# fpc_cable_all.net
KiCad netlist of a schematic drawn in EAGLE
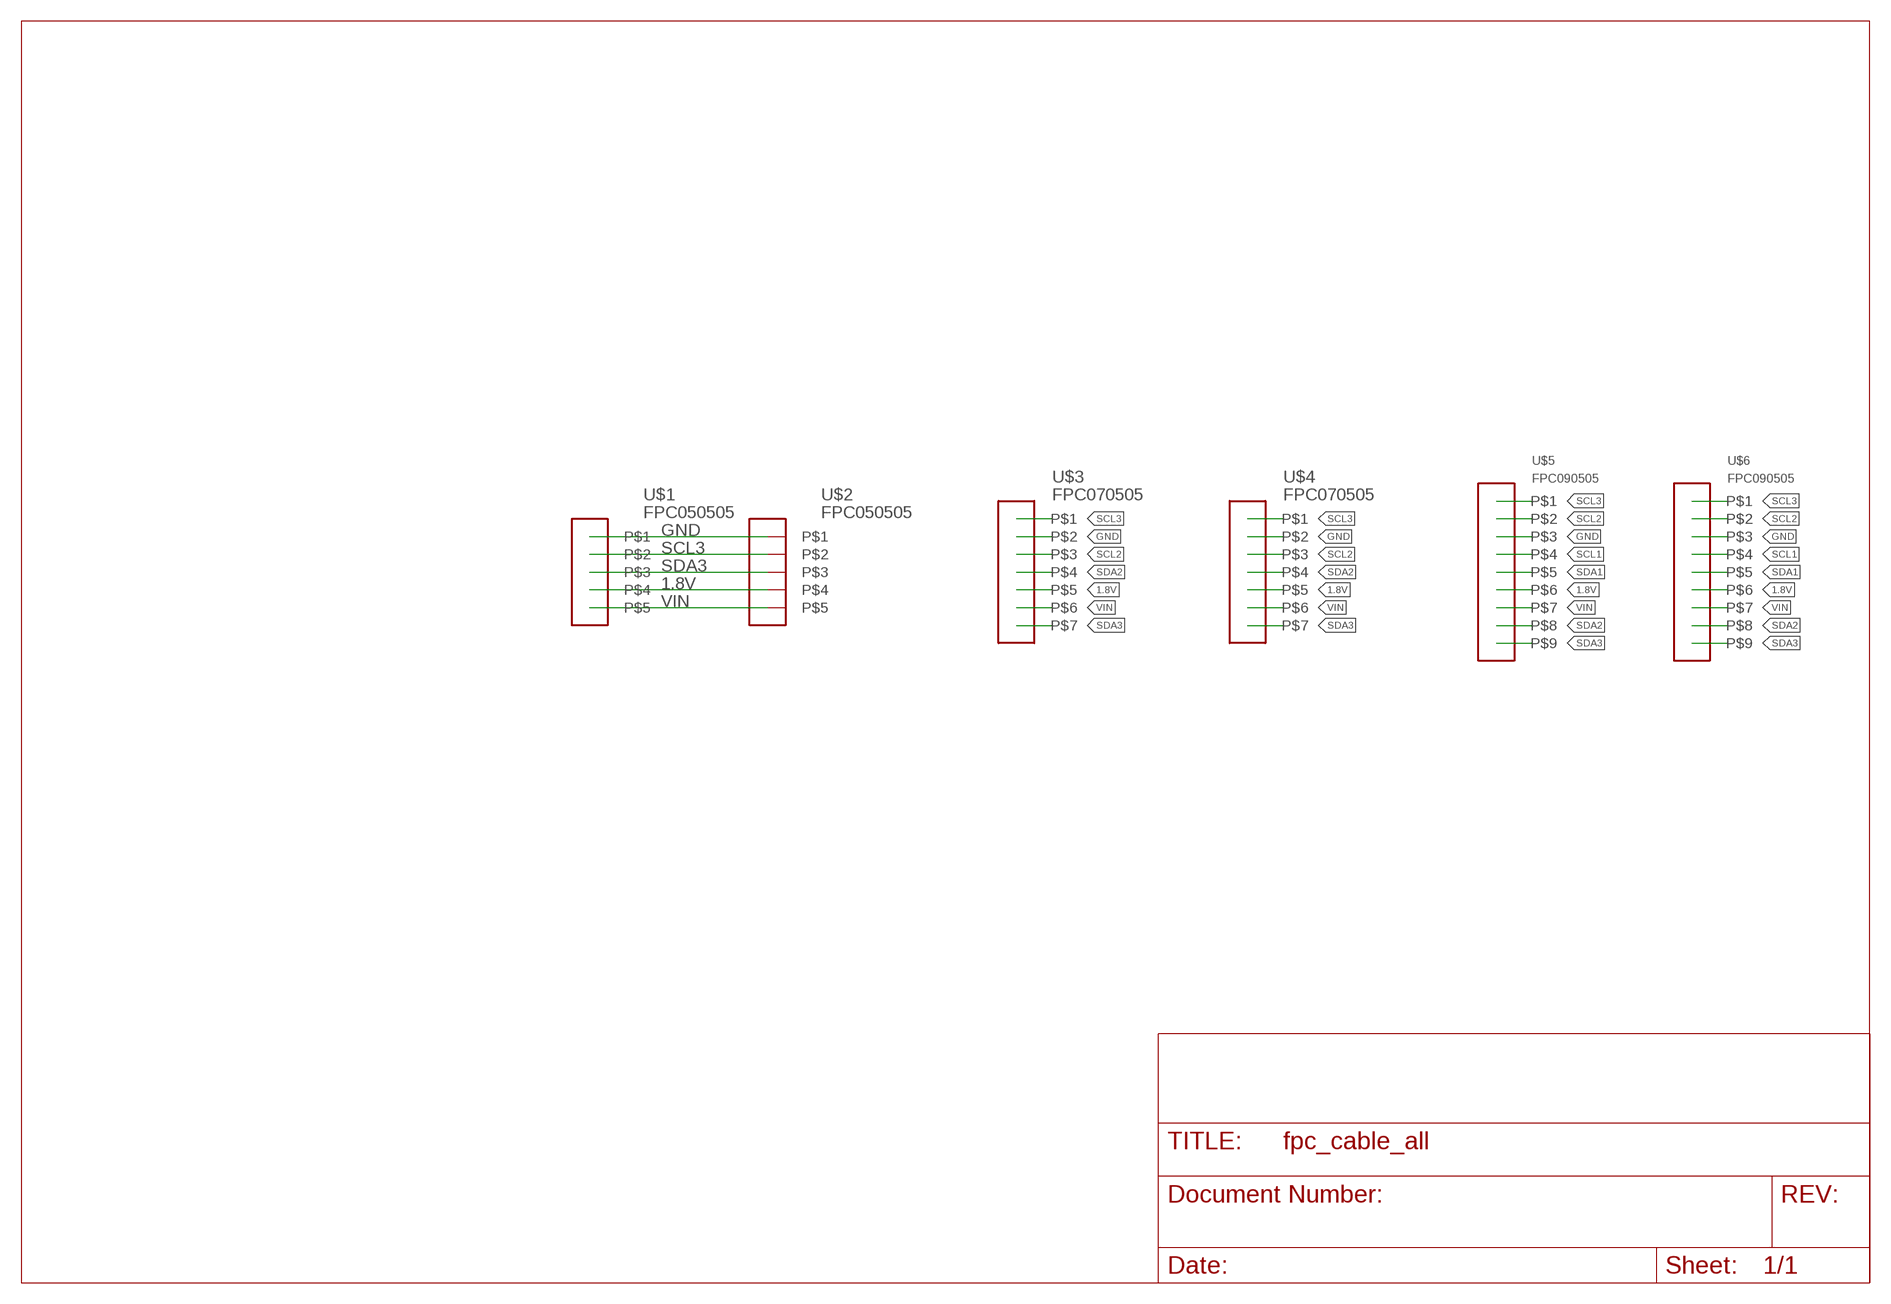
[diagram p0: schematic, sheet 1]

(export (version "E")
  (design (tool "Eeschema 10.0.6"))
  (components
    (comp (ref "U$1")
      (value "FPC050505")
      (footprint "eagle-import:FPC0505")
      (libsource (lib "eagle-import") (part "FPC050505"))
    )
    (comp (ref "U$2")
      (value "FPC050505")
      (footprint "eagle-import:FPC0505")
      (libsource (lib "eagle-import") (part "FPC050505"))
    )
    (comp (ref "U$3")
      (value "FPC070505")
      (footprint "eagle-import:FPC0705")
      (libsource (lib "eagle-import") (part "FPC070505"))
    )
    (comp (ref "U$4")
      (value "FPC070505")
      (footprint "eagle-import:FPC0705")
      (libsource (lib "eagle-import") (part "FPC070505"))
    )
    (comp (ref "U$5")
      (value "FPC090505")
      (footprint "eagle-import:FPC0905")
      (libsource (lib "eagle-import") (part "FPC090505"))
    )
    (comp (ref "U$6")
      (value "FPC090505")
      (footprint "eagle-import:FPC0905")
      (libsource (lib "eagle-import") (part "FPC090505"))
    )
  )
  (nets
    (net (code "1") (name "1.8V") (class "Default")
      (node (ref "U$1") (pin "P$4") (pinfunction "P$4_P$4") (pintype "bidirectional"))
      (node (ref "U$2") (pin "P$4") (pinfunction "P$4_P$4") (pintype "bidirectional"))
      (node (ref "U$3") (pin "P$5") (pinfunction "P$5_P$5") (pintype "bidirectional"))
      (node (ref "U$4") (pin "P$5") (pinfunction "P$5_P$5") (pintype "bidirectional"))
      (node (ref "U$5") (pin "P$6") (pinfunction "P$6_P$6") (pintype "bidirectional"))
      (node (ref "U$6") (pin "P$6") (pinfunction "P$6_P$6") (pintype "bidirectional"))
    )
    (net (code "2") (name "GND") (class "Default")
      (node (ref "U$1") (pin "P$1") (pinfunction "P$1_P$1") (pintype "bidirectional"))
      (node (ref "U$2") (pin "P$1") (pinfunction "P$1_P$1") (pintype "bidirectional"))
      (node (ref "U$3") (pin "P$2") (pinfunction "P$2_P$2") (pintype "bidirectional"))
      (node (ref "U$4") (pin "P$2") (pinfunction "P$2_P$2") (pintype "bidirectional"))
      (node (ref "U$5") (pin "P$3") (pinfunction "P$3_P$3") (pintype "bidirectional"))
      (node (ref "U$6") (pin "P$3") (pinfunction "P$3_P$3") (pintype "bidirectional"))
    )
    (net (code "3") (name "SCL1") (class "Default")
      (node (ref "U$5") (pin "P$4") (pinfunction "P$4_P$4") (pintype "bidirectional"))
      (node (ref "U$6") (pin "P$4") (pinfunction "P$4_P$4") (pintype "bidirectional"))
    )
    (net (code "4") (name "SCL2") (class "Default")
      (node (ref "U$3") (pin "P$3") (pinfunction "P$3_P$3") (pintype "bidirectional"))
      (node (ref "U$4") (pin "P$3") (pinfunction "P$3_P$3") (pintype "bidirectional"))
      (node (ref "U$5") (pin "P$2") (pinfunction "P$2_P$2") (pintype "bidirectional"))
      (node (ref "U$6") (pin "P$2") (pinfunction "P$2_P$2") (pintype "bidirectional"))
    )
    (net (code "5") (name "SCL3") (class "Default")
      (node (ref "U$1") (pin "P$2") (pinfunction "P$2_P$2") (pintype "bidirectional"))
      (node (ref "U$2") (pin "P$2") (pinfunction "P$2_P$2") (pintype "bidirectional"))
      (node (ref "U$3") (pin "P$1") (pinfunction "P$1_P$1") (pintype "bidirectional"))
      (node (ref "U$4") (pin "P$1") (pinfunction "P$1_P$1") (pintype "bidirectional"))
      (node (ref "U$5") (pin "P$1") (pinfunction "P$1_P$1") (pintype "bidirectional"))
      (node (ref "U$6") (pin "P$1") (pinfunction "P$1_P$1") (pintype "bidirectional"))
    )
    (net (code "6") (name "SDA1") (class "Default")
      (node (ref "U$5") (pin "P$5") (pinfunction "P$5_P$5") (pintype "bidirectional"))
      (node (ref "U$6") (pin "P$5") (pinfunction "P$5_P$5") (pintype "bidirectional"))
    )
    (net (code "7") (name "SDA2") (class "Default")
      (node (ref "U$3") (pin "P$4") (pinfunction "P$4_P$4") (pintype "bidirectional"))
      (node (ref "U$4") (pin "P$4") (pinfunction "P$4_P$4") (pintype "bidirectional"))
      (node (ref "U$5") (pin "P$8") (pinfunction "P$8_P$8") (pintype "bidirectional"))
      (node (ref "U$6") (pin "P$8") (pinfunction "P$8_P$8") (pintype "bidirectional"))
    )
    (net (code "8") (name "SDA3") (class "Default")
      (node (ref "U$1") (pin "P$3") (pinfunction "P$3_P$3") (pintype "bidirectional"))
      (node (ref "U$2") (pin "P$3") (pinfunction "P$3_P$3") (pintype "bidirectional"))
      (node (ref "U$3") (pin "P$7") (pinfunction "P$7_P$7") (pintype "bidirectional"))
      (node (ref "U$4") (pin "P$7") (pinfunction "P$7_P$7") (pintype "bidirectional"))
      (node (ref "U$5") (pin "P$9") (pinfunction "P$9_P$9") (pintype "bidirectional"))
      (node (ref "U$6") (pin "P$9") (pinfunction "P$9_P$9") (pintype "bidirectional"))
    )
    (net (code "9") (name "VIN") (class "Default")
      (node (ref "U$1") (pin "P$5") (pinfunction "P$5_P$5") (pintype "bidirectional"))
      (node (ref "U$2") (pin "P$5") (pinfunction "P$5_P$5") (pintype "bidirectional"))
      (node (ref "U$3") (pin "P$6") (pinfunction "P$6_P$6") (pintype "bidirectional"))
      (node (ref "U$4") (pin "P$6") (pinfunction "P$6_P$6") (pintype "bidirectional"))
      (node (ref "U$5") (pin "P$7") (pinfunction "P$7_P$7") (pintype "bidirectional"))
      (node (ref "U$6") (pin "P$7") (pinfunction "P$7_P$7") (pintype "bidirectional"))
    )
  )
)
